# Thermostat.net
KiCad netlist of a schematic drawn in EAGLE
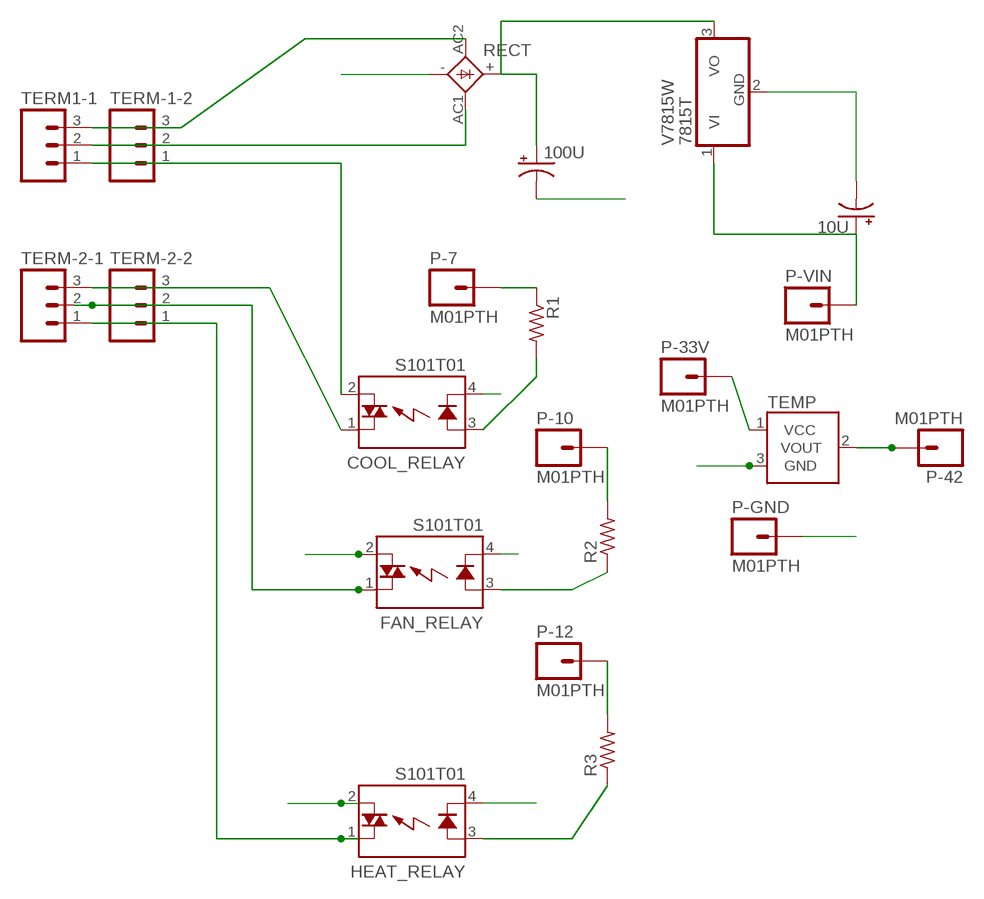
[diagram p0: schematic, sheet 1]

(export (version "E")
  (design (tool "Eeschema 10.0.6"))
  (components
    (comp (ref "10U")
      (value "CAP_POLPTH2")
      (footprint "eagle-import:CPOL-RADIAL-10UF-25V")
      (libsource (lib "eagle-import") (part "CAP_POLPTH2"))
    )
    (comp (ref "100U")
      (value "CAP_POLPTH1")
      (footprint "eagle-import:CPOL-RADIAL-100UF-25V")
      (libsource (lib "eagle-import") (part "CAP_POLPTH1"))
    )
    (comp (ref "COOL_RELAY")
      (value "S101T01")
      (footprint "eagle-import:S102T0X")
      (fields (field (name "OC_FARNELL") "unknown") (field (name "OC_NEWARK") "unknown"))
      (libsource (lib "eagle-import") (part "S?101T01"))
    )
    (comp (ref "FAN_RELAY")
      (value "S101T01")
      (footprint "eagle-import:S102T0X")
      (fields (field (name "OC_FARNELL") "unknown") (field (name "OC_NEWARK") "unknown"))
      (libsource (lib "eagle-import") (part "S?101T01"))
    )
    (comp (ref "HEAT_RELAY")
      (value "S101T01")
      (footprint "eagle-import:S102T0X")
      (fields (field (name "OC_FARNELL") "unknown") (field (name "OC_NEWARK") "unknown"))
      (libsource (lib "eagle-import") (part "S?101T01"))
    )
    (comp (ref "P-7")
      (value "M01PTH")
      (footprint "eagle-import:1X01")
      (libsource (lib "eagle-import") (part "M01PTH"))
    )
    (comp (ref "P-10")
      (value "M01PTH")
      (footprint "eagle-import:1X01")
      (libsource (lib "eagle-import") (part "M01PTH"))
    )
    (comp (ref "P-12")
      (value "M01PTH")
      (footprint "eagle-import:1X01")
      (libsource (lib "eagle-import") (part "M01PTH"))
    )
    (comp (ref "P-33V")
      (value "M01PTH")
      (footprint "eagle-import:1X01")
      (libsource (lib "eagle-import") (part "M01PTH"))
    )
    (comp (ref "P-42")
      (value "M01PTH")
      (footprint "eagle-import:1X01")
      (libsource (lib "eagle-import") (part "M01PTH"))
    )
    (comp (ref "P-GND")
      (value "M01PTH")
      (footprint "eagle-import:1X01")
      (libsource (lib "eagle-import") (part "M01PTH"))
    )
    (comp (ref "P-VIN")
      (value "M01PTH")
      (footprint "eagle-import:1X01")
      (libsource (lib "eagle-import") (part "M01PTH"))
    )
    (comp (ref "R1")
      (value "R-US_0204/2V")
      (footprint "eagle-import:0204V")
      (libsource (lib "eagle-import") (part "R-US_0204/2V"))
    )
    (comp (ref "R2")
      (value "R-US_0204/2V")
      (footprint "eagle-import:0204V")
      (libsource (lib "eagle-import") (part "R-US_0204/2V"))
    )
    (comp (ref "R3")
      (value "R-US_0204/2V")
      (footprint "eagle-import:0204V")
      (libsource (lib "eagle-import") (part "R-US_0204/2V"))
    )
    (comp (ref "RECT")
      (value "GBU4")
      (footprint "eagle-import:GBU4S")
      (libsource (lib "eagle-import") (part "GBU4"))
    )
    (comp (ref "TEMP")
      (value "TMP36GT9")
      (footprint "eagle-import:TO-92")
      (libsource (lib "eagle-import") (part "TMP36GT9"))
    )
    (comp (ref "TERM-1-2")
      (value "M031X03_NO_SILK")
      (footprint "eagle-import:1X03_NO_SILK")
      (libsource (lib "eagle-import") (part "M031X03_NO_SILK"))
    )
    (comp (ref "TERM-2-1")
      (value "M031X03_NO_SILK")
      (footprint "eagle-import:1X03_NO_SILK")
      (libsource (lib "eagle-import") (part "M031X03_NO_SILK"))
    )
    (comp (ref "TERM-2-2")
      (value "M031X03_NO_SILK")
      (footprint "eagle-import:1X03_NO_SILK")
      (libsource (lib "eagle-import") (part "M031X03_NO_SILK"))
    )
    (comp (ref "TERM1-1")
      (value "M031X03_NO_SILK")
      (footprint "eagle-import:1X03_NO_SILK")
      (libsource (lib "eagle-import") (part "M031X03_NO_SILK"))
    )
    (comp (ref "V7815W")
      (value "7815T")
      (footprint "eagle-import:TO220H")
      (libsource (lib "eagle-import") (part "78T15"))
    )
  )
  (nets
    (net (code "1") (name "/GND") (class "Default")
      (node (ref "100U") (pin "2") (pinfunction "-_2") (pintype "passive"))
      (node (ref "10U") (pin "2") (pinfunction "-_2") (pintype "passive"))
      (node (ref "COOL_RELAY") (pin "4") (pinfunction "K_4") (pintype "passive"))
      (node (ref "FAN_RELAY") (pin "4") (pinfunction "K_4") (pintype "passive"))
      (node (ref "HEAT_RELAY") (pin "4") (pinfunction "K_4") (pintype "passive"))
      (node (ref "P-GND") (pin "1") (pinfunction "1_1") (pintype "passive"))
      (node (ref "RECT") (pin "-") (pinfunction "-_-") (pintype "passive"))
      (node (ref "TEMP") (pin "3") (pinfunction "GND_3") (pintype "bidirectional"))
      (node (ref "V7815W") (pin "2") (pinfunction "GND_2") (pintype "passive"))
    )
    (net (code "2") (name "/P2") (class "Default")
      (node (ref "FAN_RELAY") (pin "2") (pinfunction "DS2_2") (pintype "passive"))
      (node (ref "HEAT_RELAY") (pin "2") (pinfunction "DS2_2") (pintype "passive"))
      (node (ref "RECT") (pin "AC1") (pinfunction "AC2_AC1") (pintype "passive"))
      (node (ref "TERM-1-2") (pin "2") (pinfunction "2_2") (pintype "passive"))
      (node (ref "TERM1-1") (pin "2") (pinfunction "2_2") (pintype "passive"))
    )
    (net (code "3") (name "Net-(10U-+)") (class "Default")
      (node (ref "10U") (pin "1") (pinfunction "+_1") (pintype "passive"))
      (node (ref "P-VIN") (pin "1") (pinfunction "1_1") (pintype "passive"))
      (node (ref "V7815W") (pin "1") (pinfunction "VI_1") (pintype "input"))
    )
    (net (code "4") (name "Net-(100U-+)") (class "Default")
      (node (ref "100U") (pin "1") (pinfunction "+_1") (pintype "passive"))
      (node (ref "RECT") (pin "+") (pinfunction "+_+") (pintype "passive"))
      (node (ref "V7815W") (pin "3") (pinfunction "VO_3") (pintype "passive"))
    )
    (net (code "5") (name "Net-(COOL_RELAY-A)") (class "Default")
      (node (ref "COOL_RELAY") (pin "3") (pinfunction "A_3") (pintype "passive"))
      (node (ref "R1") (pin "2") (pinfunction "2_2") (pintype "passive"))
    )
    (net (code "6") (name "Net-(COOL_RELAY-DS1)") (class "Default")
      (node (ref "COOL_RELAY") (pin "1") (pinfunction "DS1_1") (pintype "passive"))
      (node (ref "TERM-2-1") (pin "3") (pinfunction "3_3") (pintype "passive"))
      (node (ref "TERM-2-2") (pin "3") (pinfunction "3_3") (pintype "passive"))
    )
    (net (code "7") (name "Net-(COOL_RELAY-DS2)") (class "Default")
      (node (ref "COOL_RELAY") (pin "2") (pinfunction "DS2_2") (pintype "passive"))
      (node (ref "TERM-1-2") (pin "1") (pinfunction "1_1") (pintype "passive"))
      (node (ref "TERM1-1") (pin "1") (pinfunction "1_1") (pintype "passive"))
    )
    (net (code "8") (name "Net-(FAN_RELAY-A)") (class "Default")
      (node (ref "FAN_RELAY") (pin "3") (pinfunction "A_3") (pintype "passive"))
      (node (ref "R2") (pin "1") (pinfunction "1_1") (pintype "passive"))
    )
    (net (code "9") (name "Net-(FAN_RELAY-DS1)") (class "Default")
      (node (ref "FAN_RELAY") (pin "1") (pinfunction "DS1_1") (pintype "passive"))
      (node (ref "TERM-2-1") (pin "2") (pinfunction "2_2") (pintype "passive"))
      (node (ref "TERM-2-2") (pin "2") (pinfunction "2_2") (pintype "passive"))
    )
    (net (code "10") (name "Net-(HEAT_RELAY-A)") (class "Default")
      (node (ref "HEAT_RELAY") (pin "3") (pinfunction "A_3") (pintype "passive"))
      (node (ref "R3") (pin "1") (pinfunction "1_1") (pintype "passive"))
    )
    (net (code "11") (name "Net-(HEAT_RELAY-DS1)") (class "Default")
      (node (ref "HEAT_RELAY") (pin "1") (pinfunction "DS1_1") (pintype "passive"))
      (node (ref "TERM-2-1") (pin "1") (pinfunction "1_1") (pintype "passive"))
      (node (ref "TERM-2-2") (pin "1") (pinfunction "1_1") (pintype "passive"))
    )
    (net (code "12") (name "Net-(P-7-Pad1)") (class "Default")
      (node (ref "P-7") (pin "1") (pinfunction "1_1") (pintype "passive"))
      (node (ref "R1") (pin "1") (pinfunction "1_1") (pintype "passive"))
    )
    (net (code "13") (name "Net-(P-10-Pad1)") (class "Default")
      (node (ref "P-10") (pin "1") (pinfunction "1_1") (pintype "passive"))
      (node (ref "R2") (pin "2") (pinfunction "2_2") (pintype "passive"))
    )
    (net (code "14") (name "Net-(P-12-Pad1)") (class "Default")
      (node (ref "P-12") (pin "1") (pinfunction "1_1") (pintype "passive"))
      (node (ref "R3") (pin "2") (pinfunction "2_2") (pintype "passive"))
    )
    (net (code "15") (name "Net-(RECT-AC1)") (class "Default")
      (node (ref "RECT") (pin "AC2") (pinfunction "AC1_AC2") (pintype "passive"))
      (node (ref "TERM-1-2") (pin "3") (pinfunction "3_3") (pintype "passive"))
      (node (ref "TERM1-1") (pin "3") (pinfunction "3_3") (pintype "passive"))
    )
    (net (code "16") (name "Net-(TEMP-VCC)") (class "Default")
      (node (ref "P-33V") (pin "1") (pinfunction "1_1") (pintype "passive"))
      (node (ref "TEMP") (pin "1") (pinfunction "VCC_1") (pintype "bidirectional"))
    )
    (net (code "17") (name "Net-(TEMP-VOUT)") (class "Default")
      (node (ref "P-42") (pin "1") (pinfunction "1_1") (pintype "passive"))
      (node (ref "TEMP") (pin "2") (pinfunction "VOUT_2") (pintype "bidirectional"))
    )
  )
)
